# series_R_LED.net
KiCad netlist of a schematic drawn in EAGLE
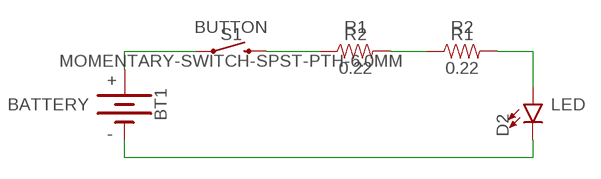
[diagram p0: schematic, sheet 1]

(export (version "E")
  (design (tool "Eeschema 10.0.6"))
  (components
    (comp (ref "BT1")
      (value "BATTERY-9V")
      (footprint "eagle-import:BATTCON_9V")
      (libsource (lib "eagle-import") (part "BATTERY-9V"))
    )
    (comp (ref "D2")
      (value "LED5MM")
      (footprint "eagle-import:LED_5MM")
      (libsource (lib "eagle-import") (part "LED5MM"))
    )
    (comp (ref "R1")
      (value "0.22")
      (footprint "eagle-import:0805")
      (libsource (lib "eagle-import") (part "0.22OHM-0805-1/4W-1%"))
    )
    (comp (ref "R2")
      (value "0.22")
      (footprint "eagle-import:0805")
      (libsource (lib "eagle-import") (part "0.22OHM-0805-1/4W-1%"))
    )
    (comp (ref "S1")
      (value "MOMENTARY-SWITCH-SPST-PTH-6.0MM")
      (footprint "eagle-import:TACTILE_SWITCH_PTH_6.0MM")
      (libsource (lib "eagle-import") (part "MOMENTARY-SWITCH-SPST-PTH-6.0MM"))
    )
  )
  (nets
    (net (code "1") (name "Net-(BT1-Pad+)") (class "Default")
      (node (ref "BT1") (pin "+") (pinfunction "+_+") (pintype "power_in"))
      (node (ref "S1") (pin "1") (pinfunction "1_1") (pintype "passive"))
    )
    (net (code "2") (name "Net-(D2-C)") (class "Default")
      (node (ref "BT1") (pin "-") (pinfunction "-_-") (pintype "power_in"))
      (node (ref "D2") (pin "K") (pinfunction "C_K") (pintype "passive"))
    )
    (net (code "3") (name "Net-(D2-PadA)") (class "Default")
      (node (ref "D2") (pin "A") (pinfunction "A_A") (pintype "passive"))
      (node (ref "R1") (pin "2") (pinfunction "2_2") (pintype "passive"))
    )
    (net (code "4") (name "Net-(R1-Pad1)") (class "Default")
      (node (ref "R1") (pin "1") (pinfunction "1_1") (pintype "passive"))
      (node (ref "R2") (pin "2") (pinfunction "2_2") (pintype "passive"))
    )
    (net (code "5") (name "Net-(S1-2)") (class "Default")
      (node (ref "R2") (pin "1") (pinfunction "1_1") (pintype "passive"))
      (node (ref "S1") (pin "3") (pinfunction "2_3") (pintype "passive"))
    )
  )
)
